# Pure_Quantiser.net
KiCad netlist of a schematic drawn in EAGLE
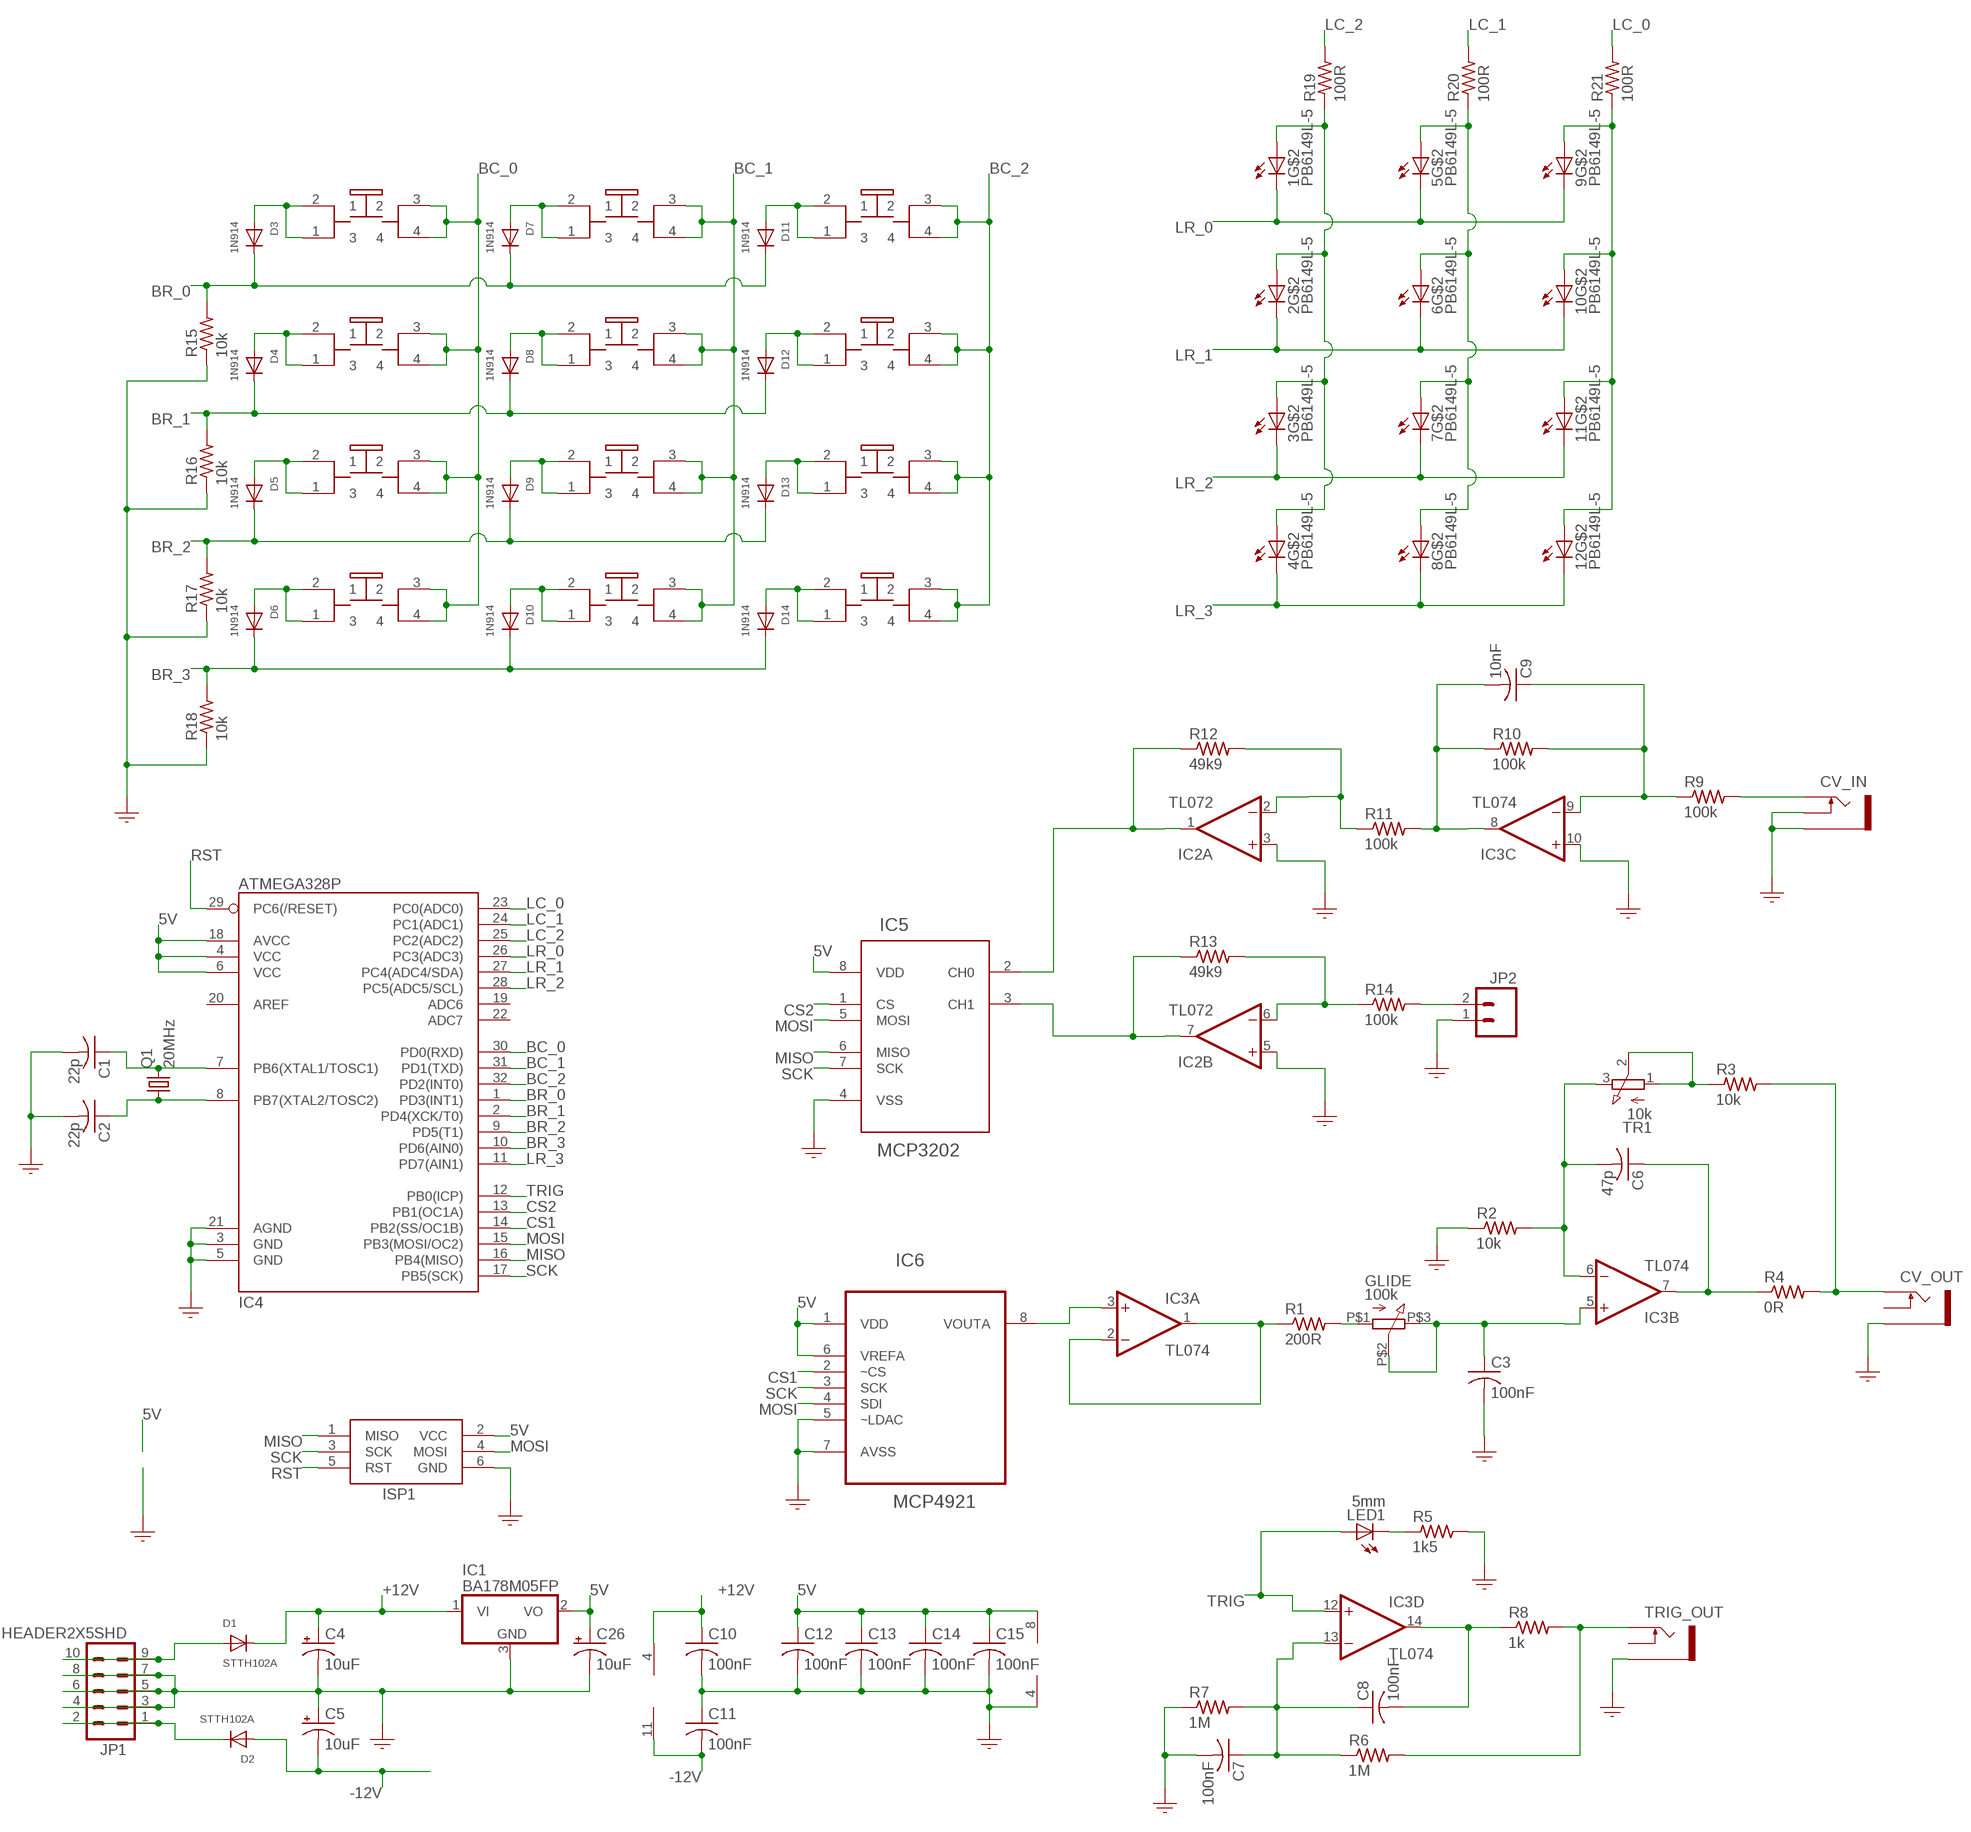
[diagram p0: schematic, sheet 1]

(export (version "E")
  (design (tool "Eeschema 10.0.6"))
  (components
    (comp (ref "1")
      (value "PB6149L-5")
      (footprint "eagle-import:PB6149L")
      (libsource (lib "eagle-import") (part "SWITCH_PUSHBUTTON_LED"))
    )
    (comp (ref "2")
      (value "PB6149L-5")
      (footprint "eagle-import:PB6149L")
      (libsource (lib "eagle-import") (part "SWITCH_PUSHBUTTON_LED"))
    )
    (comp (ref "3")
      (value "PB6149L-5")
      (footprint "eagle-import:PB6149L")
      (libsource (lib "eagle-import") (part "SWITCH_PUSHBUTTON_LED"))
    )
    (comp (ref "4")
      (value "PB6149L-5")
      (footprint "eagle-import:PB6149L")
      (libsource (lib "eagle-import") (part "SWITCH_PUSHBUTTON_LED"))
    )
    (comp (ref "5")
      (value "PB6149L-5")
      (footprint "eagle-import:PB6149L")
      (libsource (lib "eagle-import") (part "SWITCH_PUSHBUTTON_LED"))
    )
    (comp (ref "6")
      (value "PB6149L-5")
      (footprint "eagle-import:PB6149L")
      (libsource (lib "eagle-import") (part "SWITCH_PUSHBUTTON_LED"))
    )
    (comp (ref "7")
      (value "PB6149L-5")
      (footprint "eagle-import:PB6149L")
      (libsource (lib "eagle-import") (part "SWITCH_PUSHBUTTON_LED"))
    )
    (comp (ref "8")
      (value "PB6149L-5")
      (footprint "eagle-import:PB6149L")
      (libsource (lib "eagle-import") (part "SWITCH_PUSHBUTTON_LED"))
    )
    (comp (ref "9")
      (value "PB6149L-5")
      (footprint "eagle-import:PB6149L")
      (libsource (lib "eagle-import") (part "SWITCH_PUSHBUTTON_LED"))
    )
    (comp (ref "10")
      (value "PB6149L-5")
      (footprint "eagle-import:PB6149L")
      (libsource (lib "eagle-import") (part "SWITCH_PUSHBUTTON_LED"))
    )
    (comp (ref "11")
      (value "PB6149L-5")
      (footprint "eagle-import:PB6149L")
      (libsource (lib "eagle-import") (part "SWITCH_PUSHBUTTON_LED"))
    )
    (comp (ref "12")
      (value "PB6149L-5")
      (footprint "eagle-import:PB6149L")
      (libsource (lib "eagle-import") (part "SWITCH_PUSHBUTTON_LED"))
    )
    (comp (ref "C1")
      (value "22p")
      (footprint "eagle-import:C0805")
      (libsource (lib "eagle-import") (part "CAPACITOR-USC0805"))
    )
    (comp (ref "C2")
      (value "22p")
      (footprint "eagle-import:C0805")
      (libsource (lib "eagle-import") (part "CAPACITOR-USC0805"))
    )
    (comp (ref "C3")
      (value "100nF")
      (footprint "eagle-import:C0805")
      (libsource (lib "eagle-import") (part "CAPACITOR-USC0805"))
    )
    (comp (ref "C4")
      (value "10uF")
      (footprint "eagle-import:153CLV-0505")
      (libsource (lib "eagle-import") (part "CAPACITOR_POL-US153CLV-0505"))
    )
    (comp (ref "C5")
      (value "10uF")
      (footprint "eagle-import:153CLV-0505")
      (libsource (lib "eagle-import") (part "CAPACITOR_POL-US153CLV-0505"))
    )
    (comp (ref "C6")
      (value "47p")
      (footprint "eagle-import:C0805")
      (libsource (lib "eagle-import") (part "CAPACITOR-USC0805"))
    )
    (comp (ref "C7")
      (value "100nF")
      (footprint "eagle-import:C0805")
      (libsource (lib "eagle-import") (part "CAPACITOR-USC0805"))
    )
    (comp (ref "C8")
      (value "100nF")
      (footprint "eagle-import:C0805")
      (libsource (lib "eagle-import") (part "CAPACITOR-USC0805"))
    )
    (comp (ref "C9")
      (value "10nF")
      (footprint "eagle-import:C0805")
      (libsource (lib "eagle-import") (part "CAPACITOR-USC0805"))
    )
    (comp (ref "C10")
      (value "100nF")
      (footprint "eagle-import:C0805")
      (libsource (lib "eagle-import") (part "CAPACITOR-USC0805"))
    )
    (comp (ref "C11")
      (value "100nF")
      (footprint "eagle-import:C0805")
      (libsource (lib "eagle-import") (part "CAPACITOR-USC0805"))
    )
    (comp (ref "C12")
      (value "100nF")
      (footprint "eagle-import:C0805")
      (libsource (lib "eagle-import") (part "CAPACITOR-USC0805"))
    )
    (comp (ref "C13")
      (value "100nF")
      (footprint "eagle-import:C0805")
      (libsource (lib "eagle-import") (part "CAPACITOR-USC0805"))
    )
    (comp (ref "C14")
      (value "100nF")
      (footprint "eagle-import:C0805")
      (libsource (lib "eagle-import") (part "CAPACITOR-USC0805"))
    )
    (comp (ref "C15")
      (value "100nF")
      (footprint "eagle-import:C0805")
      (libsource (lib "eagle-import") (part "CAPACITOR-USC0805"))
    )
    (comp (ref "C26")
      (value "10uF")
      (footprint "eagle-import:153CLV-0505")
      (libsource (lib "eagle-import") (part "CAPACITOR_POL-US153CLV-0505"))
    )
    (comp (ref "CV_IN")
      (value "PJ301M-12")
      (footprint "eagle-import:PJ301M-12")
      (libsource (lib "eagle-import") (part "SOCKET_MONO_3.5MMPJ301M-12"))
    )
    (comp (ref "CV_OUT")
      (value "PJ301M-12")
      (footprint "eagle-import:PJ301M-12")
      (libsource (lib "eagle-import") (part "SOCKET_MONO_3.5MMPJ301M-12"))
    )
    (comp (ref "D1")
      (value "STTH102A")
      (footprint "eagle-import:SMADIODE")
      (libsource (lib "eagle-import") (part "DIODESMA"))
    )
    (comp (ref "D2")
      (value "STTH102A")
      (footprint "eagle-import:SMADIODE")
      (libsource (lib "eagle-import") (part "DIODESMA"))
    )
    (comp (ref "D3")
      (value "1N914")
      (footprint "eagle-import:DO-41")
      (libsource (lib "eagle-import") (part "DIODEDO-41"))
    )
    (comp (ref "D4")
      (value "1N914")
      (footprint "eagle-import:DO-41")
      (libsource (lib "eagle-import") (part "DIODEDO-41"))
    )
    (comp (ref "D5")
      (value "1N914")
      (footprint "eagle-import:DO-41")
      (libsource (lib "eagle-import") (part "DIODEDO-41"))
    )
    (comp (ref "D6")
      (value "1N914")
      (footprint "eagle-import:DO-41")
      (libsource (lib "eagle-import") (part "DIODEDO-41"))
    )
    (comp (ref "D7")
      (value "1N914")
      (footprint "eagle-import:DO-41")
      (libsource (lib "eagle-import") (part "DIODEDO-41"))
    )
    (comp (ref "D8")
      (value "1N914")
      (footprint "eagle-import:DO-41")
      (libsource (lib "eagle-import") (part "DIODEDO-41"))
    )
    (comp (ref "D9")
      (value "1N914")
      (footprint "eagle-import:DO-41")
      (libsource (lib "eagle-import") (part "DIODEDO-41"))
    )
    (comp (ref "D10")
      (value "1N914")
      (footprint "eagle-import:DO-41")
      (libsource (lib "eagle-import") (part "DIODEDO-41"))
    )
    (comp (ref "D11")
      (value "1N914")
      (footprint "eagle-import:DO-41")
      (libsource (lib "eagle-import") (part "DIODEDO-41"))
    )
    (comp (ref "D12")
      (value "1N914")
      (footprint "eagle-import:DO-41")
      (libsource (lib "eagle-import") (part "DIODEDO-41"))
    )
    (comp (ref "D13")
      (value "1N914")
      (footprint "eagle-import:DO-41")
      (libsource (lib "eagle-import") (part "DIODEDO-41"))
    )
    (comp (ref "D14")
      (value "1N914")
      (footprint "eagle-import:DO-41")
      (libsource (lib "eagle-import") (part "DIODEDO-41"))
    )
    (comp (ref "GLIDE")
      (value "100k")
      (footprint "eagle-import:POTENTIOMETER_9MM")
      (libsource (lib "eagle-import") (part "RESISTOR_VARIABLE9MM_POT"))
    )
    (comp (ref "IC1")
      (value "BA178M05FP")
      (footprint "eagle-import:TO252")
      (libsource (lib "eagle-import") (part "VOLTAGE_REG_POSDT05"))
    )
    (comp (ref "IC2")
      (value "TL072")
      (footprint "eagle-import:SO08")
      (libsource (lib "eagle-import") (part "OPAMP_DUALD"))
    )
    (comp (ref "IC3")
      (value "TL074")
      (footprint "eagle-import:SO14")
      (libsource (lib "eagle-import") (part "OPAMP_QUADD"))
    )
    (comp (ref "IC4")
      (value "ATMEGA328P")
      (footprint "eagle-import:TQFP32-08")
      (libsource (lib "eagle-import") (part "MICROPROCESSOR_ATMEGA328_SMT"))
    )
    (comp (ref "IC5")
      (value "MCP3202")
      (footprint "eagle-import:SOIC--8")
      (libsource (lib "eagle-import") (part "ADC_DUAL_12B_MCP3202"))
    )
    (comp (ref "IC6")
      (value "MCP4921")
      (footprint "eagle-import:SOIC8")
      (libsource (lib "eagle-import") (part "DAC_SINGLE_12B_MCP4921"))
    )
    (comp (ref "ISP1")
      (value "HEADER2X3-6")
      (footprint "eagle-import:AVRISP")
      (libsource (lib "eagle-import") (part "HEADER2X3-6"))
    )
    (comp (ref "JP1")
      (value "HEADER2X5SHD")
      (footprint "eagle-import:2X5-SHROUDED")
      (libsource (lib "eagle-import") (part "HEADER2X5SHD"))
    )
    (comp (ref "JP2")
      (value "HEADER1X2PTH")
      (footprint "eagle-import:1X02")
      (libsource (lib "eagle-import") (part "HEADER1X2PTH"))
    )
    (comp (ref "LED1")
      (value "5mm")
      (footprint "eagle-import:LED5MM")
      (libsource (lib "eagle-import") (part "LED5MM"))
    )
    (comp (ref "Q1")
      (value "20MHz")
      (footprint "eagle-import:HC49UP")
      (libsource (lib "eagle-import") (part "CRYSTALHC49UP"))
    )
    (comp (ref "R1")
      (value "200R")
      (footprint "eagle-import:R0805")
      (libsource (lib "eagle-import") (part "RESISTOR_USR0805"))
    )
    (comp (ref "R2")
      (value "10k")
      (footprint "eagle-import:R0805")
      (libsource (lib "eagle-import") (part "RESISTOR_USR0805"))
    )
    (comp (ref "R3")
      (value "10k")
      (footprint "eagle-import:R0805")
      (libsource (lib "eagle-import") (part "RESISTOR_USR0805"))
    )
    (comp (ref "R4")
      (value "0R")
      (footprint "eagle-import:R0805")
      (libsource (lib "eagle-import") (part "RESISTOR_USR0805"))
    )
    (comp (ref "R5")
      (value "1k5")
      (footprint "eagle-import:R0805")
      (libsource (lib "eagle-import") (part "RESISTOR_USR0805"))
    )
    (comp (ref "R6")
      (value "1M")
      (footprint "eagle-import:R0805")
      (libsource (lib "eagle-import") (part "RESISTOR_USR0805"))
    )
    (comp (ref "R7")
      (value "1M")
      (footprint "eagle-import:R0805")
      (libsource (lib "eagle-import") (part "RESISTOR_USR0805"))
    )
    (comp (ref "R8")
      (value "1k")
      (footprint "eagle-import:R0805")
      (libsource (lib "eagle-import") (part "RESISTOR_USR0805"))
    )
    (comp (ref "R9")
      (value "100k")
      (footprint "eagle-import:R0805")
      (libsource (lib "eagle-import") (part "RESISTOR_USR0805"))
    )
    (comp (ref "R10")
      (value "100k")
      (footprint "eagle-import:R0805")
      (libsource (lib "eagle-import") (part "RESISTOR_USR0805"))
    )
    (comp (ref "R11")
      (value "100k")
      (footprint "eagle-import:R0805")
      (libsource (lib "eagle-import") (part "RESISTOR_USR0805"))
    )
    (comp (ref "R12")
      (value "49k9")
      (footprint "eagle-import:R0805")
      (libsource (lib "eagle-import") (part "RESISTOR_USR0805"))
    )
    (comp (ref "R13")
      (value "49k9")
      (footprint "eagle-import:R0805")
      (libsource (lib "eagle-import") (part "RESISTOR_USR0805"))
    )
    (comp (ref "R14")
      (value "100k")
      (footprint "eagle-import:R0805")
      (libsource (lib "eagle-import") (part "RESISTOR_USR0805"))
    )
    (comp (ref "R15")
      (value "10k")
      (footprint "eagle-import:R0805")
      (libsource (lib "eagle-import") (part "RESISTOR_USR0805"))
    )
    (comp (ref "R16")
      (value "10k")
      (footprint "eagle-import:R0805")
      (libsource (lib "eagle-import") (part "RESISTOR_USR0805"))
    )
    (comp (ref "R17")
      (value "10k")
      (footprint "eagle-import:R0805")
      (libsource (lib "eagle-import") (part "RESISTOR_USR0805"))
    )
    (comp (ref "R18")
      (value "10k")
      (footprint "eagle-import:R0805")
      (libsource (lib "eagle-import") (part "RESISTOR_USR0805"))
    )
    (comp (ref "R19")
      (value "100R")
      (footprint "eagle-import:R0805")
      (libsource (lib "eagle-import") (part "RESISTOR_USR0805"))
    )
    (comp (ref "R20")
      (value "100R")
      (footprint "eagle-import:R0805")
      (libsource (lib "eagle-import") (part "RESISTOR_USR0805"))
    )
    (comp (ref "R21")
      (value "100R")
      (footprint "eagle-import:R0805")
      (libsource (lib "eagle-import") (part "RESISTOR_USR0805"))
    )
    (comp (ref "TR1")
      (value "10k")
      (footprint "eagle-import:TRIMMER_TH")
      (libsource (lib "eagle-import") (part "RESISTOR_VARIABLETRIMMER_TH"))
    )
    (comp (ref "TRIG_OUT")
      (value "PJ301M-12")
      (footprint "eagle-import:PJ301M-12")
      (libsource (lib "eagle-import") (part "SOCKET_MONO_3.5MMPJ301M-12"))
    )
  )
  (nets
    (net (code "1") (name "/+12V") (class "Default")
      (node (ref "C10") (pin "1") (pinfunction "1_1") (pintype "passive"))
      (node (ref "C4") (pin "+") (pinfunction "+_+") (pintype "passive"))
      (node (ref "D1") (pin "C") (pinfunction "C_C") (pintype "passive"))
      (node (ref "IC1") (pin "1") (pinfunction "VI_1") (pintype "input"))
      (node (ref "IC3") (pin "4") (pinfunction "V+_4") (pintype "power_in"))
    )
    (net (code "2") (name "/-12V") (class "Default")
      (node (ref "C11") (pin "2") (pinfunction "2_2") (pintype "passive"))
      (node (ref "C5") (pin "-") (pinfunction "-_-") (pintype "passive"))
      (node (ref "D2") (pin "A") (pinfunction "A_A") (pintype "passive"))
      (node (ref "IC3") (pin "11") (pinfunction "V-_11") (pintype "power_in"))
    )
    (net (code "3") (name "/5V") (class "Default")
      (node (ref "C12") (pin "1") (pinfunction "1_1") (pintype "passive"))
      (node (ref "C13") (pin "1") (pinfunction "1_1") (pintype "passive"))
      (node (ref "C14") (pin "1") (pinfunction "1_1") (pintype "passive"))
      (node (ref "C15") (pin "1") (pinfunction "1_1") (pintype "passive"))
      (node (ref "C26") (pin "+") (pinfunction "+_+") (pintype "passive"))
      (node (ref "IC1") (pin "2") (pinfunction "VO_2") (pintype "passive"))
      (node (ref "IC2") (pin "8") (pinfunction "V+_8") (pintype "power_in"))
      (node (ref "IC4") (pin "18") (pinfunction "AVCC_18") (pintype "bidirectional"))
      (node (ref "IC4") (pin "4") (pinfunction "VCC_4") (pintype "bidirectional"))
      (node (ref "IC4") (pin "6") (pinfunction "VCC_6") (pintype "bidirectional"))
      (node (ref "IC5") (pin "8") (pinfunction "VDD_8") (pintype "bidirectional"))
      (node (ref "IC6") (pin "1") (pinfunction "VDD_1") (pintype "power_in"))
      (node (ref "IC6") (pin "6") (pinfunction "VREFA_6") (pintype "input"))
      (node (ref "ISP1") (pin "2") (pinfunction "VCC_2") (pintype "power_in"))
    )
    (net (code "4") (name "/BC_0") (class "Default")
      (node (ref "1") (pin "3") (pinfunction "2_3") (pintype "bidirectional"))
      (node (ref "1") (pin "4") (pinfunction "4_4") (pintype "bidirectional"))
      (node (ref "2") (pin "3") (pinfunction "2_3") (pintype "bidirectional"))
      (node (ref "2") (pin "4") (pinfunction "4_4") (pintype "bidirectional"))
      (node (ref "3") (pin "3") (pinfunction "2_3") (pintype "bidirectional"))
      (node (ref "3") (pin "4") (pinfunction "4_4") (pintype "bidirectional"))
      (node (ref "4") (pin "3") (pinfunction "2_3") (pintype "bidirectional"))
      (node (ref "4") (pin "4") (pinfunction "4_4") (pintype "bidirectional"))
      (node (ref "IC4") (pin "30") (pinfunction "PD0(RXD)_30") (pintype "bidirectional"))
    )
    (net (code "5") (name "/BC_1") (class "Default")
      (node (ref "5") (pin "3") (pinfunction "2_3") (pintype "bidirectional"))
      (node (ref "5") (pin "4") (pinfunction "4_4") (pintype "bidirectional"))
      (node (ref "6") (pin "3") (pinfunction "2_3") (pintype "bidirectional"))
      (node (ref "6") (pin "4") (pinfunction "4_4") (pintype "bidirectional"))
      (node (ref "7") (pin "3") (pinfunction "2_3") (pintype "bidirectional"))
      (node (ref "7") (pin "4") (pinfunction "4_4") (pintype "bidirectional"))
      (node (ref "8") (pin "3") (pinfunction "2_3") (pintype "bidirectional"))
      (node (ref "8") (pin "4") (pinfunction "4_4") (pintype "bidirectional"))
      (node (ref "IC4") (pin "31") (pinfunction "PD1(TXD)_31") (pintype "bidirectional"))
    )
    (net (code "6") (name "/BC_2") (class "Default")
      (node (ref "10") (pin "3") (pinfunction "2_3") (pintype "bidirectional"))
      (node (ref "10") (pin "4") (pinfunction "4_4") (pintype "bidirectional"))
      (node (ref "11") (pin "3") (pinfunction "2_3") (pintype "bidirectional"))
      (node (ref "11") (pin "4") (pinfunction "4_4") (pintype "bidirectional"))
      (node (ref "12") (pin "3") (pinfunction "2_3") (pintype "bidirectional"))
      (node (ref "12") (pin "4") (pinfunction "4_4") (pintype "bidirectional"))
      (node (ref "9") (pin "3") (pinfunction "2_3") (pintype "bidirectional"))
      (node (ref "9") (pin "4") (pinfunction "4_4") (pintype "bidirectional"))
      (node (ref "IC4") (pin "32") (pinfunction "PD2(INT0)_32") (pintype "bidirectional"))
    )
    (net (code "7") (name "/BR_0") (class "Default")
      (node (ref "D11") (pin "C") (pinfunction "C_C") (pintype "passive"))
      (node (ref "D3") (pin "C") (pinfunction "C_C") (pintype "passive"))
      (node (ref "D7") (pin "C") (pinfunction "C_C") (pintype "passive"))
      (node (ref "IC4") (pin "1") (pinfunction "PD3(INT1)_1") (pintype "bidirectional"))
      (node (ref "R15") (pin "2") (pinfunction "2_2") (pintype "passive"))
    )
    (net (code "8") (name "/BR_1") (class "Default")
      (node (ref "D12") (pin "C") (pinfunction "C_C") (pintype "passive"))
      (node (ref "D4") (pin "C") (pinfunction "C_C") (pintype "passive"))
      (node (ref "D8") (pin "C") (pinfunction "C_C") (pintype "passive"))
      (node (ref "IC4") (pin "2") (pinfunction "PD4(XCK/T0)_2") (pintype "bidirectional"))
      (node (ref "R16") (pin "2") (pinfunction "2_2") (pintype "passive"))
    )
    (net (code "9") (name "/BR_2") (class "Default")
      (node (ref "D13") (pin "C") (pinfunction "C_C") (pintype "passive"))
      (node (ref "D5") (pin "C") (pinfunction "C_C") (pintype "passive"))
      (node (ref "D9") (pin "C") (pinfunction "C_C") (pintype "passive"))
      (node (ref "IC4") (pin "9") (pinfunction "PD5(T1)_9") (pintype "bidirectional"))
      (node (ref "R17") (pin "2") (pinfunction "2_2") (pintype "passive"))
    )
    (net (code "10") (name "/BR_3") (class "Default")
      (node (ref "D10") (pin "C") (pinfunction "C_C") (pintype "passive"))
      (node (ref "D14") (pin "C") (pinfunction "C_C") (pintype "passive"))
      (node (ref "D6") (pin "C") (pinfunction "C_C") (pintype "passive"))
      (node (ref "IC4") (pin "10") (pinfunction "PD6(AIN0)_10") (pintype "bidirectional"))
      (node (ref "R18") (pin "2") (pinfunction "2_2") (pintype "passive"))
    )
    (net (code "11") (name "/CS1") (class "Default")
      (node (ref "IC4") (pin "14") (pinfunction "PB2(SS/OC1B)_14") (pintype "bidirectional"))
      (node (ref "IC6") (pin "2") (pinfunction "~{CS}_2") (pintype "input"))
    )
    (net (code "12") (name "/CS2") (class "Default")
      (node (ref "IC4") (pin "13") (pinfunction "PB1(OC1A)_13") (pintype "bidirectional"))
      (node (ref "IC5") (pin "1") (pinfunction "CS_1") (pintype "bidirectional"))
    )
    (net (code "13") (name "/LC_0") (class "Default")
      (node (ref "IC4") (pin "23") (pinfunction "PC0(ADC0)_23") (pintype "bidirectional"))
      (node (ref "R21") (pin "2") (pinfunction "2_2") (pintype "passive"))
    )
    (net (code "14") (name "/LC_1") (class "Default")
      (node (ref "IC4") (pin "24") (pinfunction "PC1(ADC1)_24") (pintype "bidirectional"))
      (node (ref "R20") (pin "2") (pinfunction "2_2") (pintype "passive"))
    )
    (net (code "15") (name "/LC_2") (class "Default")
      (node (ref "IC4") (pin "25") (pinfunction "PC2(ADC2)_25") (pintype "bidirectional"))
      (node (ref "R19") (pin "2") (pinfunction "2_2") (pintype "passive"))
    )
    (net (code "16") (name "/LR_0") (class "Default")
      (node (ref "1") (pin "K") (pinfunction "C_K") (pintype "passive"))
      (node (ref "5") (pin "K") (pinfunction "C_K") (pintype "passive"))
      (node (ref "9") (pin "K") (pinfunction "C_K") (pintype "passive"))
      (node (ref "IC4") (pin "26") (pinfunction "PC3(ADC3)_26") (pintype "bidirectional"))
    )
    (net (code "17") (name "/LR_1") (class "Default")
      (node (ref "10") (pin "K") (pinfunction "C_K") (pintype "passive"))
      (node (ref "2") (pin "K") (pinfunction "C_K") (pintype "passive"))
      (node (ref "6") (pin "K") (pinfunction "C_K") (pintype "passive"))
      (node (ref "IC4") (pin "27") (pinfunction "PC4(ADC4/SDA)_27") (pintype "bidirectional"))
    )
    (net (code "18") (name "/LR_2") (class "Default")
      (node (ref "11") (pin "K") (pinfunction "C_K") (pintype "passive"))
      (node (ref "3") (pin "K") (pinfunction "C_K") (pintype "passive"))
      (node (ref "7") (pin "K") (pinfunction "C_K") (pintype "passive"))
      (node (ref "IC4") (pin "28") (pinfunction "PC5(ADC5/SCL)_28") (pintype "bidirectional"))
    )
    (net (code "19") (name "/LR_3") (class "Default")
      (node (ref "12") (pin "K") (pinfunction "C_K") (pintype "passive"))
      (node (ref "4") (pin "K") (pinfunction "C_K") (pintype "passive"))
      (node (ref "8") (pin "K") (pinfunction "C_K") (pintype "passive"))
      (node (ref "IC4") (pin "11") (pinfunction "PD7(AIN1)_11") (pintype "bidirectional"))
    )
    (net (code "20") (name "/MISO") (class "Default")
      (node (ref "IC4") (pin "16") (pinfunction "PB4(MISO)_16") (pintype "bidirectional"))
      (node (ref "IC5") (pin "6") (pinfunction "MISO_6") (pintype "bidirectional"))
      (node (ref "ISP1") (pin "1") (pinfunction "MISO_1") (pintype "input"))
    )
    (net (code "21") (name "/MOSI") (class "Default")
      (node (ref "IC4") (pin "15") (pinfunction "PB3(MOSI/OC2)_15") (pintype "bidirectional"))
      (node (ref "IC5") (pin "5") (pinfunction "MOSI_5") (pintype "bidirectional"))
      (node (ref "IC6") (pin "4") (pinfunction "SDI_4") (pintype "input"))
      (node (ref "ISP1") (pin "4") (pinfunction "MOSI_4") (pintype "output"))
    )
    (net (code "22") (name "/RST") (class "Default")
      (node (ref "IC4") (pin "29") (pinfunction "PC6(/RESET)_29") (pintype "bidirectional"))
      (node (ref "ISP1") (pin "5") (pinfunction "RST_5") (pintype "output"))
    )
    (net (code "23") (name "/SCK") (class "Default")
      (node (ref "IC4") (pin "17") (pinfunction "PB5(SCK)_17") (pintype "bidirectional"))
      (node (ref "IC5") (pin "7") (pinfunction "SCK_7") (pintype "bidirectional"))
      (node (ref "IC6") (pin "3") (pinfunction "SCK_3") (pintype "input"))
      (node (ref "ISP1") (pin "3") (pinfunction "SCK_3") (pintype "output"))
    )
    (net (code "24") (name "/TRIG") (class "Default")
      (node (ref "IC3") (pin "12") (pinfunction "+IN_12") (pintype "input"))
      (node (ref "IC4") (pin "12") (pinfunction "PB0(ICP)_12") (pintype "bidirectional"))
      (node (ref "LED1") (pin "A") (pinfunction "A_A") (pintype "passive"))
    )
    (net (code "25") (name "GND") (class "Default")
      (node (ref "C1") (pin "2") (pinfunction "2_2") (pintype "passive"))
      (node (ref "C10") (pin "2") (pinfunction "2_2") (pintype "passive"))
      (node (ref "C11") (pin "1") (pinfunction "1_1") (pintype "passive"))
      (node (ref "C12") (pin "2") (pinfunction "2_2") (pintype "passive"))
      (node (ref "C13") (pin "2") (pinfunction "2_2") (pintype "passive"))
      (node (ref "C14") (pin "2") (pinfunction "2_2") (pintype "passive"))
      (node (ref "C15") (pin "2") (pinfunction "2_2") (pintype "passive"))
      (node (ref "C2") (pin "2") (pinfunction "2_2") (pintype "passive"))
      (node (ref "C26") (pin "-") (pinfunction "-_-") (pintype "passive"))
      (node (ref "C3") (pin "2") (pinfunction "2_2") (pintype "passive"))
      (node (ref "C4") (pin "-") (pinfunction "-_-") (pintype "passive"))
      (node (ref "C5") (pin "+") (pinfunction "+_+") (pintype "passive"))
      (node (ref "C7") (pin "2") (pinfunction "2_2") (pintype "passive"))
      (node (ref "CV_IN") (pin "GND") (pinfunction "SLEEVE_GND") (pintype "passive"))
      (node (ref "CV_IN") (pin "NORM") (pinfunction "SWITCH_NORM") (pintype "passive"))
      (node (ref "CV_OUT") (pin "GND") (pinfunction "SLEEVE_GND") (pintype "passive"))
      (node (ref "IC1") (pin "3") (pinfunction "GND_3") (pintype "passive"))
      (node (ref "IC2") (pin "3") (pinfunction "+IN_3") (pintype "input"))
      (node (ref "IC2") (pin "4") (pinfunction "V-_4") (pintype "power_in"))
      (node (ref "IC2") (pin "5") (pinfunction "+IN_5") (pintype "input"))
      (node (ref "IC3") (pin "10") (pinfunction "+IN_10") (pintype "input"))
      (node (ref "IC4") (pin "21") (pinfunction "AGND_21") (pintype "bidirectional"))
      (node (ref "IC4") (pin "3") (pinfunction "GND_3") (pintype "bidirectional"))
      (node (ref "IC4") (pin "5") (pinfunction "GND_5") (pintype "bidirectional"))
      (node (ref "IC5") (pin "4") (pinfunction "VSS_4") (pintype "bidirectional"))
      (node (ref "IC6") (pin "5") (pinfunction "~{LDAC}_5") (pintype "input"))
      (node (ref "IC6") (pin "7") (pinfunction "AVSS_7") (pintype "passive"))
      (node (ref "ISP1") (pin "6") (pinfunction "GND_6") (pintype "power_in"))
      (node (ref "JP1") (pin "3") (pinfunction "3_3") (pintype "passive"))
      (node (ref "JP1") (pin "4") (pinfunction "4_4") (pintype "passive"))
      (node (ref "JP1") (pin "5") (pinfunction "5_5") (pintype "passive"))
      (node (ref "JP1") (pin "6") (pinfunction "6_6") (pintype "passive"))
      (node (ref "JP1") (pin "7") (pinfunction "7_7") (pintype "passive"))
      (node (ref "JP1") (pin "8") (pinfunction "8_8") (pintype "passive"))
      (node (ref "JP2") (pin "1") (pinfunction "1_1") (pintype "passive"))
      (node (ref "R15") (pin "1") (pinfunction "1_1") (pintype "passive"))
      (node (ref "R16") (pin "1") (pinfunction "1_1") (pintype "passive"))
      (node (ref "R17") (pin "1") (pinfunction "1_1") (pintype "passive"))
      (node (ref "R18") (pin "1") (pinfunction "1_1") (pintype "passive"))
      (node (ref "R2") (pin "1") (pinfunction "1_1") (pintype "passive"))
      (node (ref "R5") (pin "2") (pinfunction "2_2") (pintype "passive"))
      (node (ref "R7") (pin "1") (pinfunction "1_1") (pintype "passive"))
      (node (ref "TRIG_OUT") (pin "GND") (pinfunction "SLEEVE_GND") (pintype "passive"))
    )
    (net (code "26") (name "Net-(1-PadA)") (class "Default")
      (node (ref "1") (pin "A") (pinfunction "A_A") (pintype "passive"))
      (node (ref "2") (pin "A") (pinfunction "A_A") (pintype "passive"))
      (node (ref "3") (pin "A") (pinfunction "A_A") (pintype "passive"))
      (node (ref "4") (pin "A") (pinfunction "A_A") (pintype "passive"))
      (node (ref "R19") (pin "1") (pinfunction "1_1") (pintype "passive"))
    )
    (net (code "27") (name "Net-(1A-1)") (class "Default")
      (node (ref "1") (pin "1") (pinfunction "3_1") (pintype "bidirectional"))
      (node (ref "1") (pin "2") (pinfunction "1_2") (pintype "bidirectional"))
      (node (ref "D3") (pin "A") (pinfunction "A_A") (pintype "passive"))
    )
    (net (code "28") (name "Net-(2A-1)") (class "Default")
      (node (ref "2") (pin "1") (pinfunction "3_1") (pintype "bidirectional"))
      (node (ref "2") (pin "2") (pinfunction "1_2") (pintype "bidirectional"))
      (node (ref "D4") (pin "A") (pinfunction "A_A") (pintype "passive"))
    )
    (net (code "29") (name "Net-(3A-1)") (class "Default")
      (node (ref "3") (pin "1") (pinfunction "3_1") (pintype "bidirectional"))
      (node (ref "3") (pin "2") (pinfunction "1_2") (pintype "bidirectional"))
      (node (ref "D5") (pin "A") (pinfunction "A_A") (pintype "passive"))
    )
    (net (code "30") (name "Net-(4A-1)") (class "Default")
      (node (ref "4") (pin "1") (pinfunction "3_1") (pintype "bidirectional"))
      (node (ref "4") (pin "2") (pinfunction "1_2") (pintype "bidirectional"))
      (node (ref "D6") (pin "A") (pinfunction "A_A") (pintype "passive"))
    )
    (net (code "31") (name "Net-(5-PadA)") (class "Default")
      (node (ref "5") (pin "A") (pinfunction "A_A") (pintype "passive"))
      (node (ref "6") (pin "A") (pinfunction "A_A") (pintype "passive"))
      (node (ref "7") (pin "A") (pinfunction "A_A") (pintype "passive"))
      (node (ref "8") (pin "A") (pinfunction "A_A") (pintype "passive"))
      (node (ref "R20") (pin "1") (pinfunction "1_1") (pintype "passive"))
    )
    (net (code "32") (name "Net-(5A-1)") (class "Default")
      (node (ref "5") (pin "1") (pinfunction "3_1") (pintype "bidirectional"))
      (node (ref "5") (pin "2") (pinfunction "1_2") (pintype "bidirectional"))
      (node (ref "D7") (pin "A") (pinfunction "A_A") (pintype "passive"))
    )
    (net (code "33") (name "Net-(6A-1)") (class "Default")
      (node (ref "6") (pin "1") (pinfunction "3_1") (pintype "bidirectional"))
      (node (ref "6") (pin "2") (pinfunction "1_2") (pintype "bidirectional"))
      (node (ref "D8") (pin "A") (pinfunction "A_A") (pintype "passive"))
    )
    (net (code "34") (name "Net-(7A-1)") (class "Default")
      (node (ref "7") (pin "1") (pinfunction "3_1") (pintype "bidirectional"))
      (node (ref "7") (pin "2") (pinfunction "1_2") (pintype "bidirectional"))
      (node (ref "D9") (pin "A") (pinfunction "A_A") (pintype "passive"))
    )
    (net (code "35") (name "Net-(8A-1)") (class "Default")
      (node (ref "8") (pin "1") (pinfunction "3_1") (pintype "bidirectional"))
      (node (ref "8") (pin "2") (pinfunction "1_2") (pintype "bidirectional"))
      (node (ref "D10") (pin "A") (pinfunction "A_A") (pintype "passive"))
    )
    (net (code "36") (name "Net-(9A-1)") (class "Default")
      (node (ref "9") (pin "1") (pinfunction "3_1") (pintype "bidirectional"))
      (node (ref "9") (pin "2") (pinfunction "1_2") (pintype "bidirectional"))
      (node (ref "D11") (pin "A") (pinfunction "A_A") (pintype "passive"))
    )
    (net (code "37") (name "Net-(10-PadA)") (class "Default")
      (node (ref "10") (pin "A") (pinfunction "A_A") (pintype "passive"))
      (node (ref "11") (pin "A") (pinfunction "A_A") (pintype "passive"))
      (node (ref "12") (pin "A") (pinfunction "A_A") (pintype "passive"))
      (node (ref "9") (pin "A") (pinfunction "A_A") (pintype "passive"))
      (node (ref "R21") (pin "1") (pinfunction "1_1") (pintype "passive"))
    )
    (net (code "38") (name "Net-(10A-1)") (class "Default")
      (node (ref "10") (pin "1") (pinfunction "3_1") (pintype "bidirectional"))
      (node (ref "10") (pin "2") (pinfunction "1_2") (pintype "bidirectional"))
      (node (ref "D12") (pin "A") (pinfunction "A_A") (pintype "passive"))
    )
    (net (code "39") (name "Net-(11A-1)") (class "Default")
      (node (ref "11") (pin "1") (pinfunction "3_1") (pintype "bidirectional"))
      (node (ref "11") (pin "2") (pinfunction "1_2") (pintype "bidirectional"))
      (node (ref "D13") (pin "A") (pinfunction "A_A") (pintype "passive"))
    )
    (net (code "40") (name "Net-(12A-1)") (class "Default")
      (node (ref "12") (pin "1") (pinfunction "3_1") (pintype "bidirectional"))
      (node (ref "12") (pin "2") (pinfunction "1_2") (pintype "bidirectional"))
      (node (ref "D14") (pin "A") (pinfunction "A_A") (pintype "passive"))
    )
    (net (code "41") (name "Net-(CV_IN-PadTIP)") (class "Default")
      (node (ref "CV_IN") (pin "TIP") (pinfunction "TIP_TIP") (pintype "passive"))
      (node (ref "R9") (pin "2") (pinfunction "2_2") (pintype "passive"))
    )
    (net (code "42") (name "Net-(CV_OUT-PadTIP)") (class "Default")
      (node (ref "CV_OUT") (pin "TIP") (pinfunction "TIP_TIP") (pintype "passive"))
      (node (ref "R3") (pin "2") (pinfunction "2_2") (pintype "passive"))
      (node (ref "R4") (pin "2") (pinfunction "2_2") (pintype "passive"))
    )
    (net (code "43") (name "Net-(D1-PadA)") (class "Default")
      (node (ref "D1") (pin "A") (pinfunction "A_A") (pintype "passive"))
      (node (ref "JP1") (pin "10") (pinfunction "10_10") (pintype "passive"))
      (node (ref "JP1") (pin "9") (pinfunction "9_9") (pintype "passive"))
    )
    (net (code "44") (name "Net-(D2-PadC)") (class "Default")
      (node (ref "D2") (pin "C") (pinfunction "C_C") (pintype "passive"))
      (node (ref "JP1") (pin "1") (pinfunction "1_1") (pintype "passive"))
      (node (ref "JP1") (pin "2") (pinfunction "2_2") (pintype "passive"))
    )
    (net (code "45") (name "Net-(GLIDE-1)") (class "Default")
      (node (ref "GLIDE") (pin "P$1") (pinfunction "1_P$1") (pintype "passive"))
      (node (ref "R1") (pin "2") (pinfunction "2_2") (pintype "passive"))
    )
    (net (code "46") (name "Net-(GLIDE-2)") (class "Default")
      (node (ref "C3") (pin "1") (pinfunction "1_1") (pintype "passive"))
      (node (ref "GLIDE") (pin "P$2") (pinfunction "2_P$2") (pintype "passive"))
      (node (ref "GLIDE") (pin "P$3") (pinfunction "3_P$3") (pintype "passive"))
      (node (ref "IC3") (pin "5") (pinfunction "+IN_5") (pintype "input"))
    )
    (net (code "47") (name "Net-(IC2A--IN)") (class "Default")
      (node (ref "IC2") (pin "2") (pinfunction "-IN_2") (pintype "input"))
      (node (ref "R11") (pin "1") (pinfunction "1_1") (pintype "passive"))
      (node (ref "R12") (pin "2") (pinfunction "2_2") (pintype "passive"))
    )
    (net (code "48") (name "Net-(IC2A-OUT)") (class "Default")
      (node (ref "IC2") (pin "1") (pinfunction "OUT_1") (pintype "output"))
      (node (ref "IC5") (pin "2") (pinfunction "CH0_2") (pintype "bidirectional"))
      (node (ref "R12") (pin "1") (pinfunction "1_1") (pintype "passive"))
    )
    (net (code "49") (name "Net-(IC2B--IN)") (class "Default")
      (node (ref "IC2") (pin "6") (pinfunction "-IN_6") (pintype "input"))
      (node (ref "R13") (pin "2") (pinfunction "2_2") (pintype "passive"))
      (node (ref "R14") (pin "1") (pinfunction "1_1") (pintype "passive"))
    )
    (net (code "50") (name "Net-(IC2B-OUT)") (class "Default")
      (node (ref "IC2") (pin "7") (pinfunction "OUT_7") (pintype "output"))
      (node (ref "IC5") (pin "3") (pinfunction "CH1_3") (pintype "bidirectional"))
      (node (ref "R13") (pin "1") (pinfunction "1_1") (pintype "passive"))
    )
    (net (code "51") (name "Net-(IC3A-+IN)") (class "Default")
      (node (ref "IC3") (pin "3") (pinfunction "+IN_3") (pintype "input"))
      (node (ref "IC6") (pin "8") (pinfunction "VOUTA_8") (pintype "output"))
    )
    (net (code "52") (name "Net-(IC3A--IN)") (class "Default")
      (node (ref "IC3") (pin "1") (pinfunction "OUT_1") (pintype "output"))
      (node (ref "IC3") (pin "2") (pinfunction "-IN_2") (pintype "input"))
      (node (ref "R1") (pin "1") (pinfunction "1_1") (pintype "passive"))
    )
    (net (code "53") (name "Net-(IC3B--IN)") (class "Default")
      (node (ref "C6") (pin "2") (pinfunction "2_2") (pintype "passive"))
      (node (ref "IC3") (pin "6") (pinfunction "-IN_6") (pintype "input"))
      (node (ref "R2") (pin "2") (pinfunction "2_2") (pintype "passive"))
      (node (ref "TR1") (pin "3") (pinfunction "3_3") (pintype "passive"))
    )
    (net (code "54") (name "Net-(IC3B-OUT)") (class "Default")
      (node (ref "C6") (pin "1") (pinfunction "1_1") (pintype "passive"))
      (node (ref "IC3") (pin "7") (pinfunction "OUT_7") (pintype "output"))
      (node (ref "R4") (pin "1") (pinfunction "1_1") (pintype "passive"))
    )
    (net (code "55") (name "Net-(IC3C--IN)") (class "Default")
      (node (ref "C9") (pin "1") (pinfunction "1_1") (pintype "passive"))
      (node (ref "IC3") (pin "9") (pinfunction "-IN_9") (pintype "input"))
      (node (ref "R10") (pin "2") (pinfunction "2_2") (pintype "passive"))
      (node (ref "R9") (pin "1") (pinfunction "1_1") (pintype "passive"))
    )
    (net (code "56") (name "Net-(IC3C-OUT)") (class "Default")
      (node (ref "C9") (pin "2") (pinfunction "2_2") (pintype "passive"))
      (node (ref "IC3") (pin "8") (pinfunction "OUT_8") (pintype "output"))
      (node (ref "R10") (pin "1") (pinfunction "1_1") (pintype "passive"))
      (node (ref "R11") (pin "2") (pinfunction "2_2") (pintype "passive"))
    )
    (net (code "57") (name "Net-(IC3D--IN)") (class "Default")
      (node (ref "C7") (pin "1") (pinfunction "1_1") (pintype "passive"))
      (node (ref "C8") (pin "1") (pinfunction "1_1") (pintype "passive"))
      (node (ref "IC3") (pin "13") (pinfunction "-IN_13") (pintype "input"))
      (node (ref "R6") (pin "1") (pinfunction "1_1") (pintype "passive"))
      (node (ref "R7") (pin "2") (pinfunction "2_2") (pintype "passive"))
    )
    (net (code "58") (name "Net-(IC3D-OUT)") (class "Default")
      (node (ref "C8") (pin "2") (pinfunction "2_2") (pintype "passive"))
      (node (ref "IC3") (pin "14") (pinfunction "OUT_14") (pintype "output"))
      (node (ref "R8") (pin "1") (pinfunction "1_1") (pintype "passive"))
    )
    (net (code "59") (name "Net-(IC4-PB6(XTAL1{slash}TOSC1))") (class "Default")
      (node (ref "C1") (pin "1") (pinfunction "1_1") (pintype "passive"))
      (node (ref "IC4") (pin "7") (pinfunction "PB6(XTAL1/TOSC1)_7") (pintype "bidirectional"))
      (node (ref "Q1") (pin "2") (pinfunction "2_2") (pintype "passive"))
    )
    (net (code "60") (name "Net-(IC4-PB7(XTAL2{slash}TOSC2))") (class "Default")
      (node (ref "C2") (pin "1") (pinfunction "1_1") (pintype "passive"))
      (node (ref "IC4") (pin "8") (pinfunction "PB7(XTAL2/TOSC2)_8") (pintype "bidirectional"))
      (node (ref "Q1") (pin "1") (pinfunction "1_1") (pintype "passive"))
    )
    (net (code "61") (name "Net-(JP2-Pad2)") (class "Default")
      (node (ref "JP2") (pin "2") (pinfunction "2_2") (pintype "passive"))
      (node (ref "R14") (pin "2") (pinfunction "2_2") (pintype "passive"))
    )
    (net (code "62") (name "Net-(LED1-C)") (class "Default")
      (node (ref "LED1") (pin "K") (pinfunction "C_K") (pintype "passive"))
      (node (ref "R5") (pin "1") (pinfunction "1_1") (pintype "passive"))
    )
    (net (code "63") (name "Net-(R3-Pad1)") (class "Default")
      (node (ref "R3") (pin "1") (pinfunction "1_1") (pintype "passive"))
      (node (ref "TR1") (pin "1") (pinfunction "1_1") (pintype "passive"))
      (node (ref "TR1") (pin "2") (pinfunction "2_2") (pintype "passive"))
    )
    (net (code "64") (name "Net-(R6-Pad2)") (class "Default")
      (node (ref "R6") (pin "2") (pinfunction "2_2") (pintype "passive"))
      (node (ref "R8") (pin "2") (pinfunction "2_2") (pintype "passive"))
      (node (ref "TRIG_OUT") (pin "TIP") (pinfunction "TIP_TIP") (pintype "passive"))
    )
    (net (code "65") (name "unconnected-(CV_OUT-SWITCH-PadNORM)") (class "Default")
      (node (ref "CV_OUT") (pin "NORM") (pinfunction "SWITCH_NORM") (pintype "passive"))
    )
    (net (code "66") (name "unconnected-(IC4-ADC6-Pad19)") (class "Default")
      (node (ref "IC4") (pin "19") (pinfunction "ADC6_19") (pintype "bidirectional"))
    )
    (net (code "67") (name "unconnected-(IC4-ADC7-Pad22)") (class "Default")
      (node (ref "IC4") (pin "22") (pinfunction "ADC7_22") (pintype "bidirectional"))
    )
    (net (code "68") (name "unconnected-(IC4-AREF-Pad20)") (class "Default")
      (node (ref "IC4") (pin "20") (pinfunction "AREF_20") (pintype "bidirectional"))
    )
    (net (code "69") (name "unconnected-(TRIG_OUT-SWITCH-PadNORM)") (class "Default")
      (node (ref "TRIG_OUT") (pin "NORM") (pinfunction "SWITCH_NORM") (pintype "passive"))
    )
  )
)
